# mcu_peripheral.net
KiCad netlist of a schematic drawn in Altium Designer
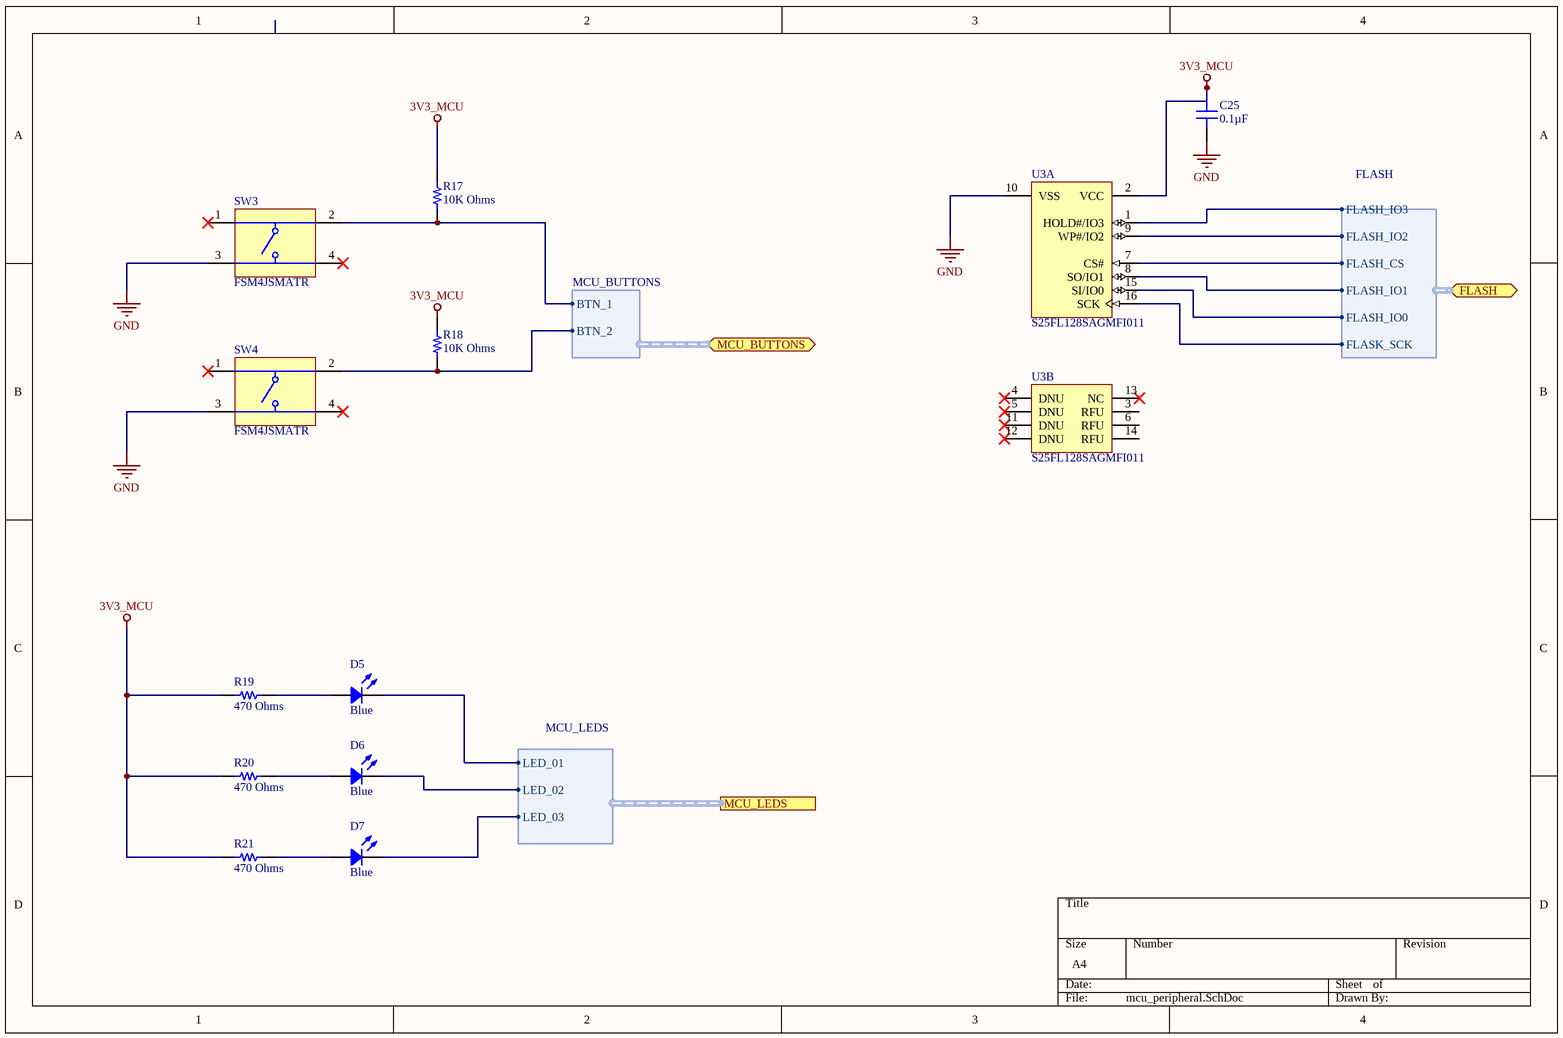
[diagram p0: mcu_peripheral.SchDoc]

(export (version "E")
  (design (tool "Eeschema 10.0.6"))
  (components
    (comp (ref "C25")
      (value "0.1µF")
      (footprint "CAP 0603_1608")
      (description "CAP CER 0.1UF 50V X7R 0603")
      (fields (field (name "PART NUMBER") "C0603C104K5RAC7411") (field (name "MANUFACTURER") "KEMET"))
      (libsource (lib "Celestial Altium Library - altium_library (2)") (part "Capacitor"))
    )
    (comp (ref "D5")
      (value "Blue")
      (footprint "LED 0603_1608 BLUE")
      (description "LED BLUE 0603 SMD")
      (fields
        (field (name "PART NUMBER") "VLMB1300-GS08")
        (field (name "MANUFACTURER") "Vishay Semiconductor Opto Division")
      )
      (libsource (lib "Celestial Altium Library - altium_library (2)") (part "LED"))
    )
    (comp (ref "D6")
      (value "Blue")
      (footprint "LED 0603_1608 BLUE")
      (description "LED BLUE 0603 SMD")
      (fields
        (field (name "PART NUMBER") "VLMB1300-GS08")
        (field (name "MANUFACTURER") "Vishay Semiconductor Opto Division")
      )
      (libsource (lib "Celestial Altium Library - altium_library (2)") (part "LED"))
    )
    (comp (ref "D7")
      (value "Blue")
      (footprint "LED 0603_1608 BLUE")
      (description "LED BLUE 0603 SMD")
      (fields
        (field (name "PART NUMBER") "VLMB1300-GS08")
        (field (name "MANUFACTURER") "Vishay Semiconductor Opto Division")
      )
      (libsource (lib "Celestial Altium Library - altium_library (2)") (part "LED"))
    )
    (comp (ref "R17")
      (value "10K Ohms")
      (footprint "RES 0603_1608")
      (description "RES SMD 470 OHM 5% 1/4W 0603")
      (fields (field (name "PART NUMBER") "CRCW0603470RJNEAHP") (field (name "MANUFACTURER") "Vishay Dale"))
      (libsource (lib "Celestial Altium Library - altium_library (2)") (part "Resistor"))
    )
    (comp (ref "R18")
      (value "10K Ohms")
      (footprint "RES 0603_1608")
      (description "RES SMD 470 OHM 5% 1/4W 0603")
      (fields (field (name "PART NUMBER") "CRCW0603470RJNEAHP") (field (name "MANUFACTURER") "Vishay Dale"))
      (libsource (lib "Celestial Altium Library - altium_library (2)") (part "Resistor"))
    )
    (comp (ref "R19")
      (value "470 Ohms")
      (footprint "RES 0603_1608")
      (description "RES SMD 470 OHM 5% 1/4W 0603")
      (fields (field (name "PART NUMBER") "CRCW0603470RJNEAHP") (field (name "MANUFACTURER") "Vishay Dale"))
      (libsource (lib "Celestial Altium Library - altium_library (2)") (part "Resistor"))
    )
    (comp (ref "R20")
      (value "470 Ohms")
      (footprint "RES 0603_1608")
      (description "RES SMD 470 OHM 5% 1/4W 0603")
      (fields (field (name "PART NUMBER") "CRCW0603470RJNEAHP") (field (name "MANUFACTURER") "Vishay Dale"))
      (libsource (lib "Celestial Altium Library - altium_library (2)") (part "Resistor"))
    )
    (comp (ref "R21")
      (value "470 Ohms")
      (footprint "RES 0603_1608")
      (description "RES SMD 470 OHM 5% 1/4W 0603")
      (fields (field (name "PART NUMBER") "CRCW0603470RJNEAHP") (field (name "MANUFACTURER") "Vishay Dale"))
      (libsource (lib "Celestial Altium Library - altium_library (2)") (part "Resistor"))
    )
    (comp (ref "SW3")
      (value "FSM4JSMATR")
      (footprint "TECO-FSM4JSMATR_V")
      (description "Micro Miniature Push Button Switch FSM JSM, 50 mA, -35 to 85 degC, 4-Pin SMD, RoHS, Tape and Reel")
      (fields (field (name "MANUFACTURER") "TE Connectivity"))
      (libsource (lib "Altium Content Vault") (part "SW-SPST-4_A"))
    )
    (comp (ref "SW4")
      (value "FSM4JSMATR")
      (footprint "TECO-FSM4JSMATR_V")
      (description "Micro Miniature Push Button Switch FSM JSM, 50 mA, -35 to 85 degC, 4-Pin SMD, RoHS, Tape and Reel")
      (fields (field (name "MANUFACTURER") "TE Connectivity"))
      (libsource (lib "Altium Content Vault") (part "SW-SPST-4_A"))
    )
    (comp (ref "U3")
      (value "S25FL128SAGMFI011")
      (footprint "SPSN-SOIC-16_L")
      (fields (field (name "MANUFACTURER") "Spansion"))
      (libsource (lib "") (part "SPSN-S25FL128S-16_1"))
    )
  )
  (nets
    (net (code "4") (name "/BTN_1") (class "Default")
      (node (ref "R17") (pin "1") (pinfunction "1_1") (pintype "passive"))
      (node (ref "SW3") (pin "2") (pinfunction "2_2") (pintype "passive"))
    )
    (net (code "5") (name "/BTN_2") (class "Default")
      (node (ref "R18") (pin "1") (pinfunction "1_1") (pintype "passive"))
      (node (ref "SW4") (pin "2") (pinfunction "2_2") (pintype "passive"))
    )
    (net (code "6") (name "/FLASH_CS") (class "Default")
      (node (ref "U3") (pin "7") (pinfunction "CS#_7") (pintype "input"))
    )
    (net (code "7") (name "/FLASH_IO0") (class "Default")
      (node (ref "U3") (pin "15") (pinfunction "SI/IO0_15") (pintype "bidirectional"))
    )
    (net (code "8") (name "/FLASH_IO1") (class "Default")
      (node (ref "U3") (pin "8") (pinfunction "SO/IO1_8") (pintype "bidirectional"))
    )
    (net (code "9") (name "/FLASH_IO2") (class "Default")
      (node (ref "U3") (pin "9") (pinfunction "WP#/IO2_9") (pintype "bidirectional"))
    )
    (net (code "10") (name "/FLASH_IO3") (class "Default")
      (node (ref "U3") (pin "1") (pinfunction "HOLD#/IO3_1") (pintype "bidirectional"))
    )
    (net (code "11") (name "/FLASK_SCK") (class "Default")
      (node (ref "U3") (pin "16") (pinfunction "SCK_16") (pintype "input"))
    )
    (net (code "12") (name "/LED_01") (class "Default")
      (node (ref "D5") (pin "2") (pinfunction "2_2") (pintype "passive"))
    )
    (net (code "13") (name "/LED_02") (class "Default")
      (node (ref "D6") (pin "2") (pinfunction "2_2") (pintype "passive"))
    )
    (net (code "14") (name "/LED_03") (class "Default")
      (node (ref "D7") (pin "2") (pinfunction "2_2") (pintype "passive"))
    )
    (net (code "18") (name "3V3_MCU") (class "Default")
      (node (ref "C25") (pin "2") (pinfunction "2_2") (pintype "passive"))
      (node (ref "R17") (pin "2") (pinfunction "2_2") (pintype "passive"))
      (node (ref "R18") (pin "2") (pinfunction "2_2") (pintype "passive"))
      (node (ref "R19") (pin "1") (pinfunction "1_1") (pintype "passive"))
      (node (ref "R20") (pin "1") (pinfunction "1_1") (pintype "passive"))
      (node (ref "R21") (pin "1") (pinfunction "1_1") (pintype "passive"))
      (node (ref "U3") (pin "2") (pinfunction "VCC_2") (pintype "power_in"))
    )
    (net (code "19") (name "GND") (class "Default")
      (node (ref "C25") (pin "1") (pinfunction "1_1") (pintype "passive"))
      (node (ref "SW3") (pin "3") (pinfunction "3_3") (pintype "passive"))
      (node (ref "SW4") (pin "3") (pinfunction "3_3") (pintype "passive"))
      (node (ref "U3") (pin "10") (pinfunction "VSS_10") (pintype "power_in"))
    )
    (net (code "20") (name "Net-(D5-Pad1)") (class "Default")
      (node (ref "D5") (pin "1") (pinfunction "1_1") (pintype "passive"))
      (node (ref "R19") (pin "2") (pinfunction "2_2") (pintype "passive"))
    )
    (net (code "21") (name "Net-(D6-Pad1)") (class "Default")
      (node (ref "D6") (pin "1") (pinfunction "1_1") (pintype "passive"))
      (node (ref "R20") (pin "2") (pinfunction "2_2") (pintype "passive"))
    )
    (net (code "22") (name "Net-(D7-Pad1)") (class "Default")
      (node (ref "D7") (pin "1") (pinfunction "1_1") (pintype "passive"))
      (node (ref "R21") (pin "2") (pinfunction "2_2") (pintype "passive"))
    )
    (net (code "23") (name "unconnected-(SW3-Pad1)") (class "Default")
      (node (ref "SW3") (pin "1") (pinfunction "1_1") (pintype "passive+no_connect"))
    )
    (net (code "24") (name "unconnected-(SW3-Pad4)") (class "Default")
      (node (ref "SW3") (pin "4") (pinfunction "4_4") (pintype "passive+no_connect"))
    )
    (net (code "25") (name "unconnected-(SW4-Pad1)") (class "Default")
      (node (ref "SW4") (pin "1") (pinfunction "1_1") (pintype "passive+no_connect"))
    )
    (net (code "26") (name "unconnected-(SW4-Pad4)") (class "Default")
      (node (ref "SW4") (pin "4") (pinfunction "4_4") (pintype "passive+no_connect"))
    )
    (net (code "27") (name "unconnected-(U3B-DNU-Pad4)") (class "Default")
      (node (ref "U3") (pin "4") (pinfunction "DNU_4") (pintype "passive+no_connect"))
    )
    (net (code "28") (name "unconnected-(U3B-DNU-Pad5)") (class "Default")
      (node (ref "U3") (pin "5") (pinfunction "DNU_5") (pintype "passive+no_connect"))
    )
    (net (code "29") (name "unconnected-(U3B-DNU-Pad11)") (class "Default")
      (node (ref "U3") (pin "11") (pinfunction "DNU_11") (pintype "passive+no_connect"))
    )
    (net (code "30") (name "unconnected-(U3B-DNU-Pad12)") (class "Default")
      (node (ref "U3") (pin "12") (pinfunction "DNU_12") (pintype "passive+no_connect"))
    )
    (net (code "31") (name "unconnected-(U3B-NC-Pad13)") (class "Default")
      (node (ref "U3") (pin "13") (pinfunction "NC_13") (pintype "passive+no_connect"))
    )
    (net (code "32") (name "unconnected-(U3B-RFU-Pad3)") (class "Default")
      (node (ref "U3") (pin "3") (pinfunction "RFU_3") (pintype "passive"))
    )
    (net (code "33") (name "unconnected-(U3B-RFU-Pad6)") (class "Default")
      (node (ref "U3") (pin "6") (pinfunction "RFU_6") (pintype "passive"))
    )
    (net (code "34") (name "unconnected-(U3B-RFU-Pad14)") (class "Default")
      (node (ref "U3") (pin "14") (pinfunction "RFU_14") (pintype "passive"))
    )
  )
)
